# feedback.net
KiCad netlist of a schematic drawn in Altium Designer
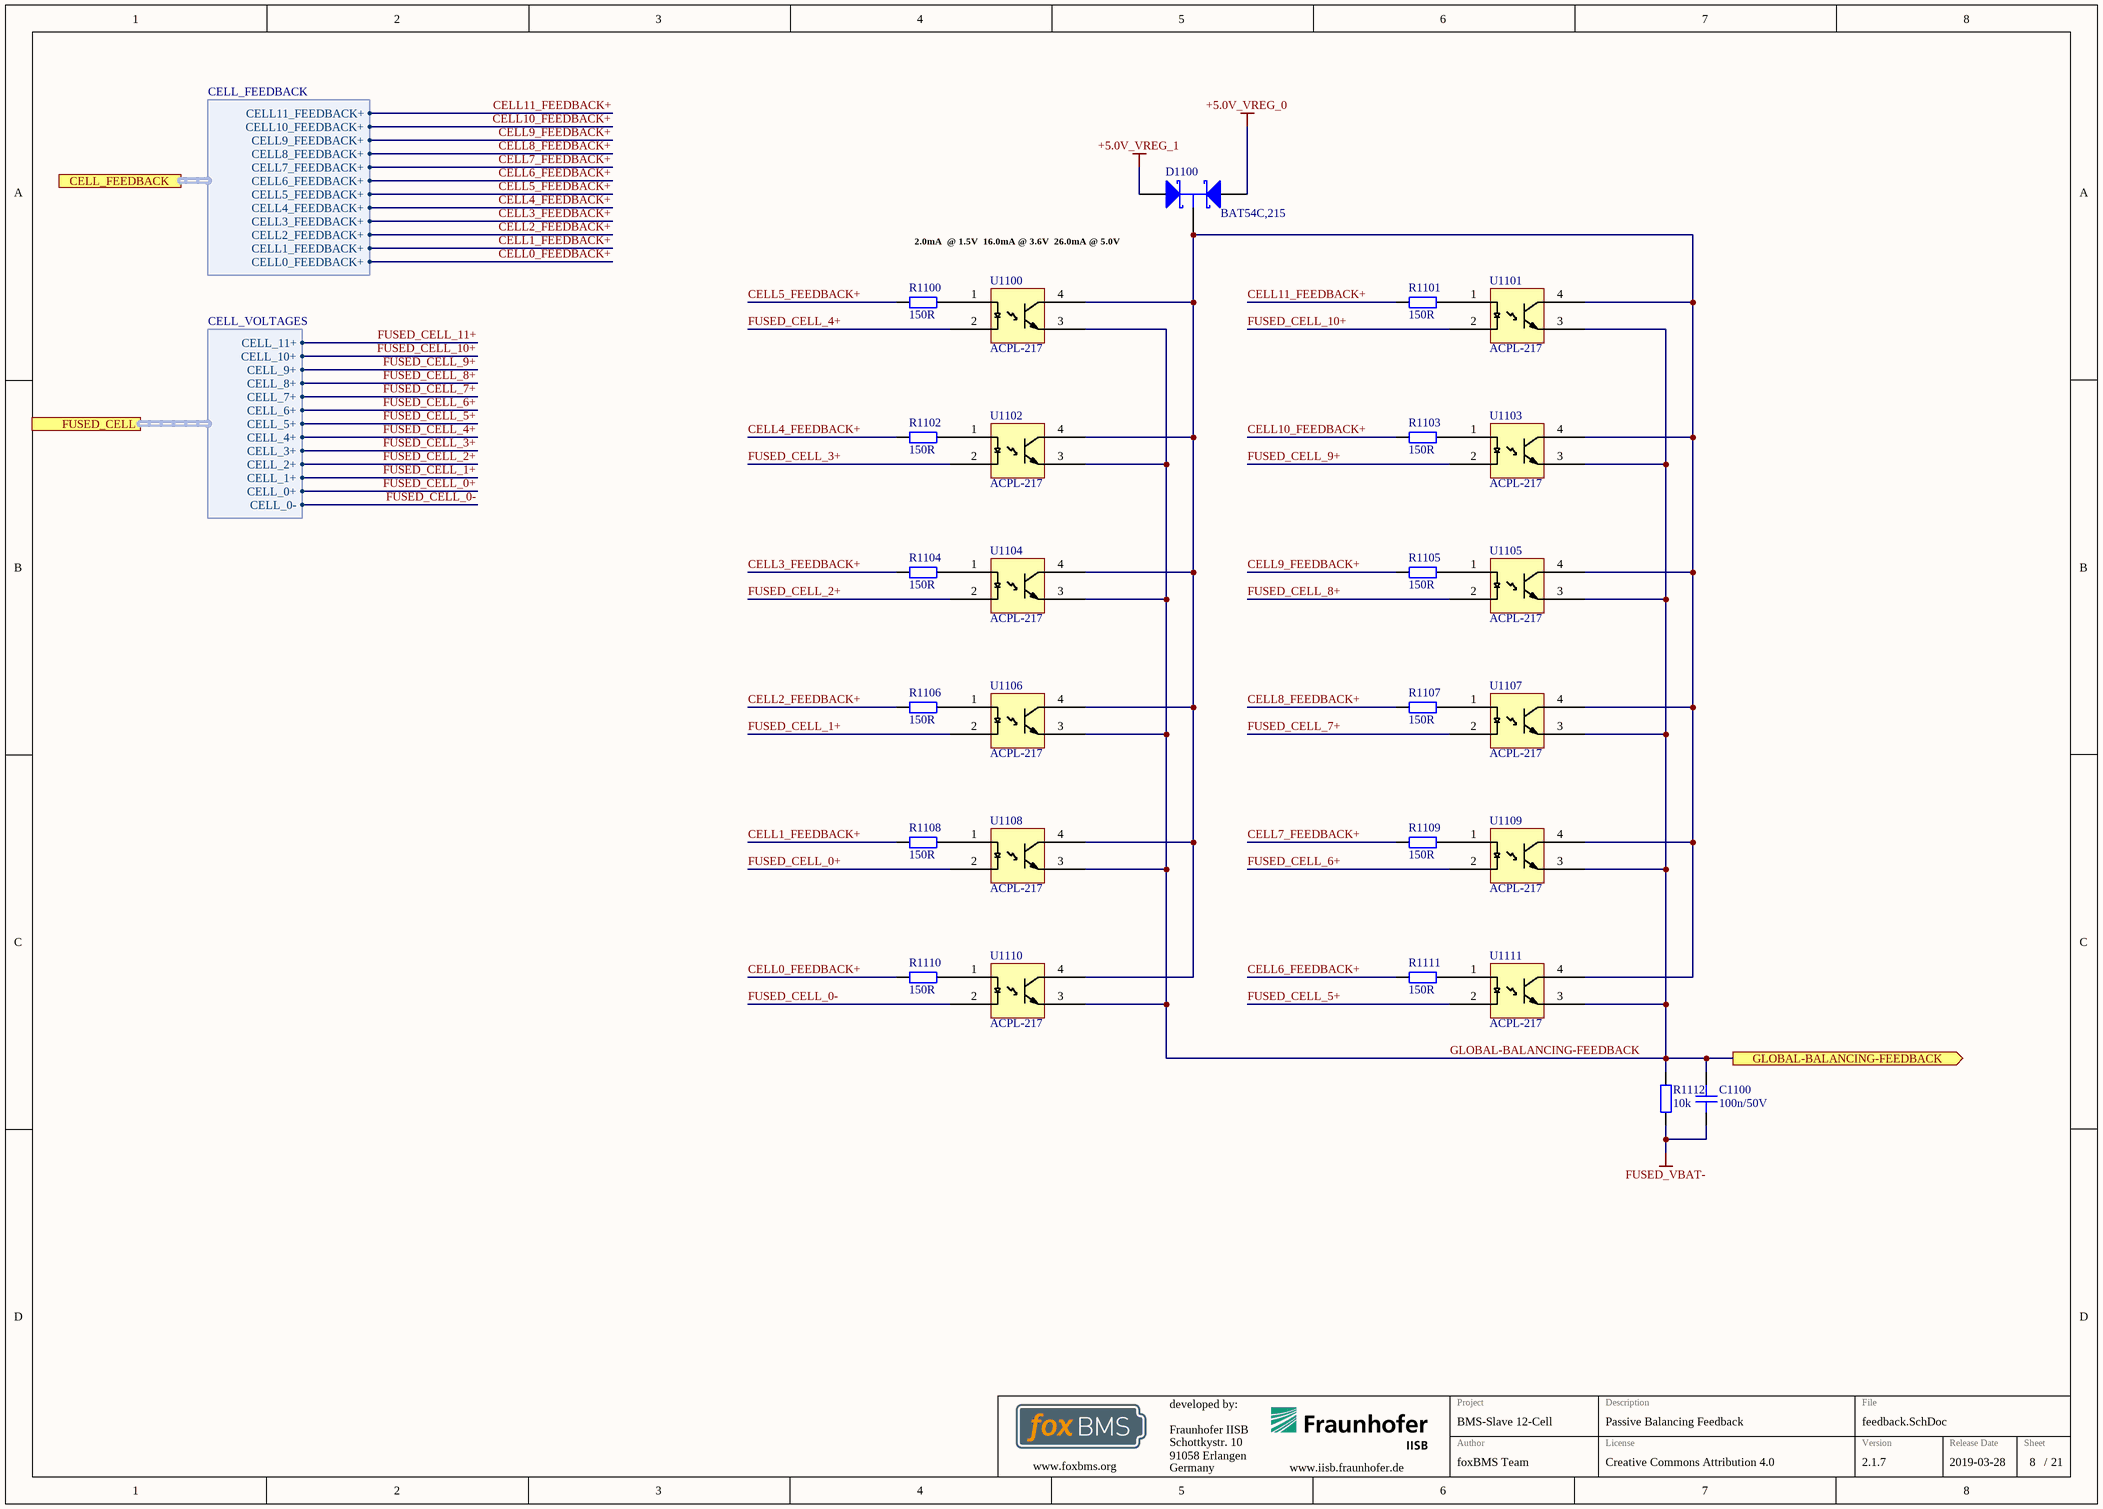
[diagram p0: feedback.SchDoc]

(export (version "E")
  (design (tool "Eeschema 10.0.6"))
  (components
    (comp (ref "C1100")
      (value "100n/50V")
      (footprint "CAPC1608X08N")
      (description "MLCC")
      (fields (field (name "PART NUMBER") "gen_C_ceramic_100n_50V_X7R_0603"))
      (libsource (lib "OE750") (part "C"))
    )
    (comp (ref "D1100")
      (value "BAT54C,215")
      (footprint "NXP-SOT23-3_V")
      (description "Schottky Barrier Diode, 30 V, 3-Pin SOT23, RoHS, Tape and Reel")
      (fields (field (name "MANUFACTURER") "NXP Semiconductors"))
      (libsource (lib "Altium Content Vault") (part "DSKY-AAK-3"))
    )
    (comp (ref "R1100")
      (value "150R")
      (footprint "RESC1608X05N")
      (description "SMD Resistor 150R 0603")
      (fields (field (name "PART NUMBER") "gen_R_150R_0603") (field (name "TOLERANCE") "1%"))
      (libsource (lib "OE750") (part "R"))
    )
    (comp (ref "R1101")
      (value "150R")
      (footprint "RESC1608X05N")
      (description "SMD Resistor 150R 0603")
      (fields (field (name "PART NUMBER") "gen_R_150R_0603") (field (name "TOLERANCE") "1%"))
      (libsource (lib "OE750") (part "R"))
    )
    (comp (ref "R1102")
      (value "150R")
      (footprint "RESC1608X05N")
      (description "SMD Resistor 150R 0603")
      (fields (field (name "PART NUMBER") "gen_R_150R_0603") (field (name "TOLERANCE") "1%"))
      (libsource (lib "OE750") (part "R"))
    )
    (comp (ref "R1103")
      (value "150R")
      (footprint "RESC1608X05N")
      (description "SMD Resistor 150R 0603")
      (fields (field (name "PART NUMBER") "gen_R_150R_0603") (field (name "TOLERANCE") "1%"))
      (libsource (lib "OE750") (part "R"))
    )
    (comp (ref "R1104")
      (value "150R")
      (footprint "RESC1608X05N")
      (description "SMD Resistor 150R 0603")
      (fields (field (name "PART NUMBER") "gen_R_150R_0603") (field (name "TOLERANCE") "1%"))
      (libsource (lib "OE750") (part "R"))
    )
    (comp (ref "R1105")
      (value "150R")
      (footprint "RESC1608X05N")
      (description "SMD Resistor 150R 0603")
      (fields (field (name "PART NUMBER") "gen_R_150R_0603") (field (name "TOLERANCE") "1%"))
      (libsource (lib "OE750") (part "R"))
    )
    (comp (ref "R1106")
      (value "150R")
      (footprint "RESC1608X05N")
      (description "SMD Resistor 150R 0603")
      (fields (field (name "PART NUMBER") "gen_R_150R_0603") (field (name "TOLERANCE") "1%"))
      (libsource (lib "OE750") (part "R"))
    )
    (comp (ref "R1107")
      (value "150R")
      (footprint "RESC1608X05N")
      (description "SMD Resistor 150R 0603")
      (fields (field (name "PART NUMBER") "gen_R_150R_0603") (field (name "TOLERANCE") "1%"))
      (libsource (lib "OE750") (part "R"))
    )
    (comp (ref "R1108")
      (value "150R")
      (footprint "RESC1608X05N")
      (description "SMD Resistor 150R 0603")
      (fields (field (name "PART NUMBER") "gen_R_150R_0603") (field (name "TOLERANCE") "1%"))
      (libsource (lib "OE750") (part "R"))
    )
    (comp (ref "R1109")
      (value "150R")
      (footprint "RESC1608X05N")
      (description "SMD Resistor 150R 0603")
      (fields (field (name "PART NUMBER") "gen_R_150R_0603") (field (name "TOLERANCE") "1%"))
      (libsource (lib "OE750") (part "R"))
    )
    (comp (ref "R1110")
      (value "150R")
      (footprint "RESC1608X05N")
      (description "SMD Resistor 150R 0603")
      (fields (field (name "PART NUMBER") "gen_R_150R_0603") (field (name "TOLERANCE") "1%"))
      (libsource (lib "OE750") (part "R"))
    )
    (comp (ref "R1111")
      (value "150R")
      (footprint "RESC1608X05N")
      (description "SMD Resistor 150R 0603")
      (fields (field (name "PART NUMBER") "gen_R_150R_0603") (field (name "TOLERANCE") "1%"))
      (libsource (lib "OE750") (part "R"))
    )
    (comp (ref "R1112")
      (value "10k")
      (footprint "RESC1608X05N")
      (description "SMD Resistor 10k 0603")
      (fields (field (name "PART NUMBER") "gen_R_10k_0603") (field (name "TOLERANCE") "1%"))
      (libsource (lib "OE750") (part "R"))
    )
    (comp (ref "U1100")
      (value "ACPL-217")
      (footprint "SOIC127P700X220-4N")
      (description "Optocoupler, Transistor Output, 1 Channel")
      (fields (field (name "PART NUMBER") "ACPL-217-56BE") (field (name "MANUFACTURER") "Broadcom Limited"))
      (libsource (lib "OE750") (part "ACPL-217"))
    )
    (comp (ref "U1101")
      (value "ACPL-217")
      (footprint "SOIC127P700X220-4N")
      (description "Optocoupler, Transistor Output, 1 Channel")
      (fields (field (name "PART NUMBER") "ACPL-217-56BE") (field (name "MANUFACTURER") "Broadcom Limited"))
      (libsource (lib "OE750") (part "ACPL-217"))
    )
    (comp (ref "U1102")
      (value "ACPL-217")
      (footprint "SOIC127P700X220-4N")
      (description "Optocoupler, Transistor Output, 1 Channel")
      (fields (field (name "PART NUMBER") "ACPL-217-56BE") (field (name "MANUFACTURER") "Broadcom Limited"))
      (libsource (lib "OE750") (part "ACPL-217"))
    )
    (comp (ref "U1103")
      (value "ACPL-217")
      (footprint "SOIC127P700X220-4N")
      (description "Optocoupler, Transistor Output, 1 Channel")
      (fields (field (name "PART NUMBER") "ACPL-217-56BE") (field (name "MANUFACTURER") "Broadcom Limited"))
      (libsource (lib "OE750") (part "ACPL-217"))
    )
    (comp (ref "U1104")
      (value "ACPL-217")
      (footprint "SOIC127P700X220-4N")
      (description "Optocoupler, Transistor Output, 1 Channel")
      (fields (field (name "PART NUMBER") "ACPL-217-56BE") (field (name "MANUFACTURER") "Broadcom Limited"))
      (libsource (lib "OE750") (part "ACPL-217"))
    )
    (comp (ref "U1105")
      (value "ACPL-217")
      (footprint "SOIC127P700X220-4N")
      (description "Optocoupler, Transistor Output, 1 Channel")
      (fields (field (name "PART NUMBER") "ACPL-217-56BE") (field (name "MANUFACTURER") "Broadcom Limited"))
      (libsource (lib "OE750") (part "ACPL-217"))
    )
    (comp (ref "U1106")
      (value "ACPL-217")
      (footprint "SOIC127P700X220-4N")
      (description "Optocoupler, Transistor Output, 1 Channel")
      (fields (field (name "PART NUMBER") "ACPL-217-56BE") (field (name "MANUFACTURER") "Broadcom Limited"))
      (libsource (lib "OE750") (part "ACPL-217"))
    )
    (comp (ref "U1107")
      (value "ACPL-217")
      (footprint "SOIC127P700X220-4N")
      (description "Optocoupler, Transistor Output, 1 Channel")
      (fields (field (name "PART NUMBER") "ACPL-217-56BE") (field (name "MANUFACTURER") "Broadcom Limited"))
      (libsource (lib "OE750") (part "ACPL-217"))
    )
    (comp (ref "U1108")
      (value "ACPL-217")
      (footprint "SOIC127P700X220-4N")
      (description "Optocoupler, Transistor Output, 1 Channel")
      (fields (field (name "PART NUMBER") "ACPL-217-56BE") (field (name "MANUFACTURER") "Broadcom Limited"))
      (libsource (lib "OE750") (part "ACPL-217"))
    )
    (comp (ref "U1109")
      (value "ACPL-217")
      (footprint "SOIC127P700X220-4N")
      (description "Optocoupler, Transistor Output, 1 Channel")
      (fields (field (name "PART NUMBER") "ACPL-217-56BE") (field (name "MANUFACTURER") "Broadcom Limited"))
      (libsource (lib "OE750") (part "ACPL-217"))
    )
    (comp (ref "U1110")
      (value "ACPL-217")
      (footprint "SOIC127P700X220-4N")
      (description "Optocoupler, Transistor Output, 1 Channel")
      (fields (field (name "PART NUMBER") "ACPL-217-56BE") (field (name "MANUFACTURER") "Broadcom Limited"))
      (libsource (lib "OE750") (part "ACPL-217"))
    )
    (comp (ref "U1111")
      (value "ACPL-217")
      (footprint "SOIC127P700X220-4N")
      (description "Optocoupler, Transistor Output, 1 Channel")
      (fields (field (name "PART NUMBER") "ACPL-217-56BE") (field (name "MANUFACTURER") "Broadcom Limited"))
      (libsource (lib "OE750") (part "ACPL-217"))
    )
  )
  (nets
    (net (code "3") (name "+5.0V_VREG_0") (class "Default")
      (node (ref "D1100") (pin "2") (pinfunction "A_2") (pintype "passive"))
    )
    (net (code "4") (name "+5.0V_VREG_1") (class "Default")
      (node (ref "D1100") (pin "1") (pinfunction "A_1") (pintype "passive"))
    )
    (net (code "5") (name "/CELL0_FEEDBACK+") (class "Default")
      (node (ref "R1110") (pin "1") (pinfunction "1_1") (pintype "passive"))
    )
    (net (code "6") (name "/CELL1_FEEDBACK+") (class "Default")
      (node (ref "R1108") (pin "1") (pinfunction "1_1") (pintype "passive"))
    )
    (net (code "7") (name "/CELL2_FEEDBACK+") (class "Default")
      (node (ref "R1106") (pin "1") (pinfunction "1_1") (pintype "passive"))
    )
    (net (code "8") (name "/CELL3_FEEDBACK+") (class "Default")
      (node (ref "R1104") (pin "1") (pinfunction "1_1") (pintype "passive"))
    )
    (net (code "9") (name "/CELL4_FEEDBACK+") (class "Default")
      (node (ref "R1102") (pin "1") (pinfunction "1_1") (pintype "passive"))
    )
    (net (code "10") (name "/CELL5_FEEDBACK+") (class "Default")
      (node (ref "R1100") (pin "1") (pinfunction "1_1") (pintype "passive"))
    )
    (net (code "11") (name "/CELL6_FEEDBACK+") (class "Default")
      (node (ref "R1111") (pin "1") (pinfunction "1_1") (pintype "passive"))
    )
    (net (code "12") (name "/CELL7_FEEDBACK+") (class "Default")
      (node (ref "R1109") (pin "1") (pinfunction "1_1") (pintype "passive"))
    )
    (net (code "13") (name "/CELL8_FEEDBACK+") (class "Default")
      (node (ref "R1107") (pin "1") (pinfunction "1_1") (pintype "passive"))
    )
    (net (code "14") (name "/CELL9_FEEDBACK+") (class "Default")
      (node (ref "R1105") (pin "1") (pinfunction "1_1") (pintype "passive"))
    )
    (net (code "15") (name "/CELL10_FEEDBACK+") (class "Default")
      (node (ref "R1103") (pin "1") (pinfunction "1_1") (pintype "passive"))
    )
    (net (code "16") (name "/CELL11_FEEDBACK+") (class "Default")
      (node (ref "R1101") (pin "1") (pinfunction "1_1") (pintype "passive"))
    )
    (net (code "17") (name "/FUSED_CELL_0+") (class "Default")
      (node (ref "U1108") (pin "2") (pintype "power_in"))
    )
    (net (code "18") (name "/FUSED_CELL_0-") (class "Default")
      (node (ref "U1110") (pin "2") (pintype "power_in"))
    )
    (net (code "19") (name "/FUSED_CELL_1+") (class "Default")
      (node (ref "U1106") (pin "2") (pintype "power_in"))
    )
    (net (code "20") (name "/FUSED_CELL_2+") (class "Default")
      (node (ref "U1104") (pin "2") (pintype "power_in"))
    )
    (net (code "21") (name "/FUSED_CELL_3+") (class "Default")
      (node (ref "U1102") (pin "2") (pintype "power_in"))
    )
    (net (code "22") (name "/FUSED_CELL_4+") (class "Default")
      (node (ref "U1100") (pin "2") (pintype "power_in"))
    )
    (net (code "23") (name "/FUSED_CELL_5+") (class "Default")
      (node (ref "U1111") (pin "2") (pintype "power_in"))
    )
    (net (code "24") (name "/FUSED_CELL_6+") (class "Default")
      (node (ref "U1109") (pin "2") (pintype "power_in"))
    )
    (net (code "25") (name "/FUSED_CELL_7+") (class "Default")
      (node (ref "U1107") (pin "2") (pintype "power_in"))
    )
    (net (code "26") (name "/FUSED_CELL_8+") (class "Default")
      (node (ref "U1105") (pin "2") (pintype "power_in"))
    )
    (net (code "27") (name "/FUSED_CELL_9+") (class "Default")
      (node (ref "U1103") (pin "2") (pintype "power_in"))
    )
    (net (code "28") (name "/FUSED_CELL_10+") (class "Default")
      (node (ref "U1101") (pin "2") (pintype "power_in"))
    )
    (net (code "30") (name "/GLOBAL-BALANCING-FEEDBACK") (class "Default")
      (node (ref "C1100") (pin "2") (pinfunction "2_2") (pintype "passive"))
      (node (ref "R1112") (pin "1") (pinfunction "1_1") (pintype "passive"))
      (node (ref "U1100") (pin "3") (pintype "passive"))
      (node (ref "U1101") (pin "3") (pintype "passive"))
      (node (ref "U1102") (pin "3") (pintype "passive"))
      (node (ref "U1103") (pin "3") (pintype "passive"))
      (node (ref "U1104") (pin "3") (pintype "passive"))
      (node (ref "U1105") (pin "3") (pintype "passive"))
      (node (ref "U1106") (pin "3") (pintype "passive"))
      (node (ref "U1107") (pin "3") (pintype "passive"))
      (node (ref "U1108") (pin "3") (pintype "passive"))
      (node (ref "U1109") (pin "3") (pintype "passive"))
      (node (ref "U1110") (pin "3") (pintype "passive"))
      (node (ref "U1111") (pin "3") (pintype "passive"))
    )
    (net (code "33") (name "FUSED_VBAT-") (class "Default")
      (node (ref "C1100") (pin "1") (pinfunction "1_1") (pintype "passive"))
      (node (ref "R1112") (pin "2") (pinfunction "2_2") (pintype "passive"))
    )
    (net (code "34") (name "Net-(D1100-K)") (class "Default")
      (node (ref "D1100") (pin "3") (pinfunction "K_3") (pintype "passive"))
      (node (ref "U1100") (pin "4") (pintype "passive"))
      (node (ref "U1101") (pin "4") (pintype "passive"))
      (node (ref "U1102") (pin "4") (pintype "passive"))
      (node (ref "U1103") (pin "4") (pintype "passive"))
      (node (ref "U1104") (pin "4") (pintype "passive"))
      (node (ref "U1105") (pin "4") (pintype "passive"))
      (node (ref "U1106") (pin "4") (pintype "passive"))
      (node (ref "U1107") (pin "4") (pintype "passive"))
      (node (ref "U1108") (pin "4") (pintype "passive"))
      (node (ref "U1109") (pin "4") (pintype "passive"))
      (node (ref "U1110") (pin "4") (pintype "passive"))
      (node (ref "U1111") (pin "4") (pintype "passive"))
    )
    (net (code "35") (name "Net-(R1100-Pad2)") (class "Default")
      (node (ref "R1100") (pin "2") (pinfunction "2_2") (pintype "passive"))
      (node (ref "U1100") (pin "1") (pintype "passive"))
    )
    (net (code "36") (name "Net-(R1101-Pad2)") (class "Default")
      (node (ref "R1101") (pin "2") (pinfunction "2_2") (pintype "passive"))
      (node (ref "U1101") (pin "1") (pintype "passive"))
    )
    (net (code "37") (name "Net-(R1102-Pad2)") (class "Default")
      (node (ref "R1102") (pin "2") (pinfunction "2_2") (pintype "passive"))
      (node (ref "U1102") (pin "1") (pintype "passive"))
    )
    (net (code "38") (name "Net-(R1103-Pad2)") (class "Default")
      (node (ref "R1103") (pin "2") (pinfunction "2_2") (pintype "passive"))
      (node (ref "U1103") (pin "1") (pintype "passive"))
    )
    (net (code "39") (name "Net-(R1104-Pad2)") (class "Default")
      (node (ref "R1104") (pin "2") (pinfunction "2_2") (pintype "passive"))
      (node (ref "U1104") (pin "1") (pintype "passive"))
    )
    (net (code "40") (name "Net-(R1105-Pad2)") (class "Default")
      (node (ref "R1105") (pin "2") (pinfunction "2_2") (pintype "passive"))
      (node (ref "U1105") (pin "1") (pintype "passive"))
    )
    (net (code "41") (name "Net-(R1106-Pad2)") (class "Default")
      (node (ref "R1106") (pin "2") (pinfunction "2_2") (pintype "passive"))
      (node (ref "U1106") (pin "1") (pintype "passive"))
    )
    (net (code "42") (name "Net-(R1107-Pad2)") (class "Default")
      (node (ref "R1107") (pin "2") (pinfunction "2_2") (pintype "passive"))
      (node (ref "U1107") (pin "1") (pintype "passive"))
    )
    (net (code "43") (name "Net-(R1108-Pad2)") (class "Default")
      (node (ref "R1108") (pin "2") (pinfunction "2_2") (pintype "passive"))
      (node (ref "U1108") (pin "1") (pintype "passive"))
    )
    (net (code "44") (name "Net-(R1109-Pad2)") (class "Default")
      (node (ref "R1109") (pin "2") (pinfunction "2_2") (pintype "passive"))
      (node (ref "U1109") (pin "1") (pintype "passive"))
    )
    (net (code "45") (name "Net-(R1110-Pad2)") (class "Default")
      (node (ref "R1110") (pin "2") (pinfunction "2_2") (pintype "passive"))
      (node (ref "U1110") (pin "1") (pintype "passive"))
    )
    (net (code "46") (name "Net-(R1111-Pad2)") (class "Default")
      (node (ref "R1111") (pin "2") (pinfunction "2_2") (pintype "passive"))
      (node (ref "U1111") (pin "1") (pintype "passive"))
    )
  )
)
